# 04_Mechanical.net
KiCad netlist of a schematic drawn in Altium Designer
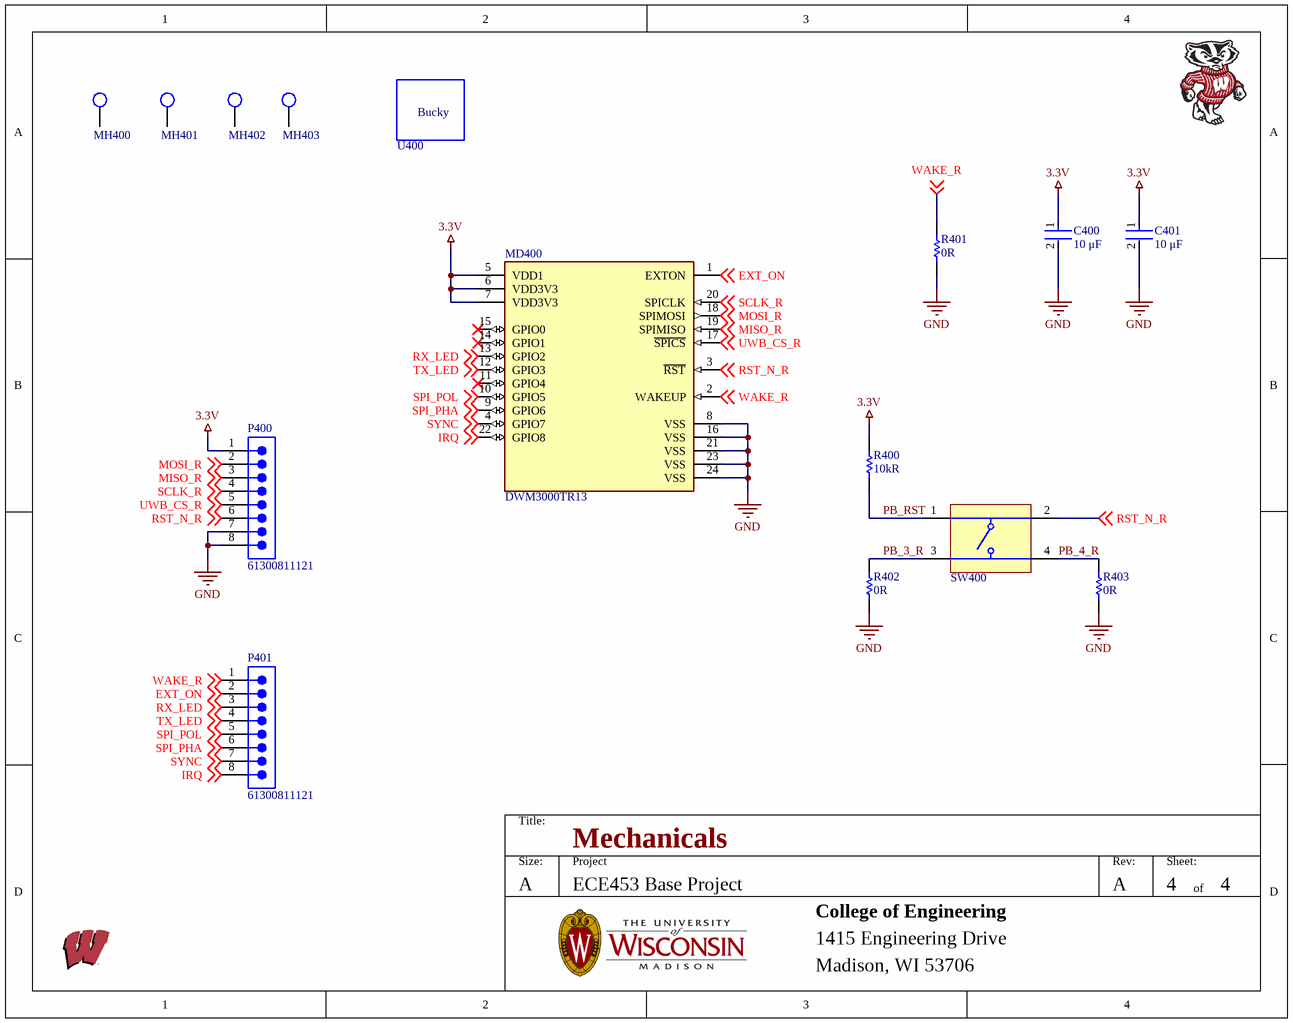
[diagram p0: 04_Mechanical.SchDoc]

(export (version "E")
  (design (tool "Eeschema 10.0.6"))
  (components
    (comp (ref "C400")
      (value "10 μF")
      (footprint "FP-C0805C-DG-MFG")
      (description "SMD Comm X5R, Ceramic, 10 uF, 10%, 10 V, X5R, SMD, MLCC, Temperature Stable, Class II, 0805")
      (fields (field (name "TOLERANCE") "10%"))
      (libsource (lib "Altium Content Vault") (part "11868f565c42a9108669ba33697ecf6"))
    )
    (comp (ref "C401")
      (value "10 μF")
      (footprint "FP-C0805C-DG-MFG")
      (description "SMD Comm X5R, Ceramic, 10 uF, 10%, 10 V, X5R, SMD, MLCC, Temperature Stable, Class II, 0805")
      (fields (field (name "TOLERANCE") "10%"))
      (libsource (lib "Altium Content Vault") (part "11868f565c42a9108669ba33697ecf6"))
    )
    (comp (ref "MD400")
      (value "DWM3000TR13")
      (footprint "FP-DWM3000TR13-MFG")
      (description "DWM3000 module Freq: 7.9872 GHz 6.8Mbps SPI 2.5-3.6V 8 GPIO's")
      (libsource (lib "Altium Content Vault") (part "094cfe914922597e69cd10df7811a9c"))
    )
    (comp (ref "MH400")
      (value "MHOLE_2_55MM")
      (footprint "MHOLE_2_55MM")
      (description "Mounting Holde")
      (fields (field (name "MANUFACTURER PART NUMBER") "UW MTHOLE"))
      (libsource (lib "ECE453_S24") (part "MHOLE_2_55MM"))
    )
    (comp (ref "MH401")
      (value "MHOLE_2_55MM")
      (footprint "MHOLE_2_55MM")
      (description "Mounting Holde")
      (fields (field (name "MANUFACTURER PART NUMBER") "UW MTHOLE"))
      (libsource (lib "ECE453_S24") (part "MHOLE_2_55MM"))
    )
    (comp (ref "MH402")
      (value "MHOLE_2_55MM")
      (footprint "MHOLE_2_55MM")
      (description "Mounting Holde")
      (fields (field (name "MANUFACTURER PART NUMBER") "UW MTHOLE"))
      (libsource (lib "ECE453_S24") (part "MHOLE_2_55MM"))
    )
    (comp (ref "MH403")
      (value "MHOLE_2_55MM")
      (footprint "MHOLE_2_55MM")
      (description "Mounting Holde")
      (fields (field (name "MANUFACTURER PART NUMBER") "UW MTHOLE"))
      (libsource (lib "ECE453_S24") (part "MHOLE_2_55MM"))
    )
    (comp (ref "P400")
      (value "61300811121")
      (footprint "61300811121")
      (fields (field (name "MANUFACTURER") "Wurth Electronics"))
      (libsource (lib "Altium Content Vault") (part "Header_Male_1R_08P"))
    )
    (comp (ref "P401")
      (value "61300811121")
      (footprint "61300811121")
      (fields (field (name "MANUFACTURER") "Wurth Electronics"))
      (libsource (lib "Altium Content Vault") (part "Header_Male_1R_08P"))
    )
    (comp (ref "R400")
      (value "10kR")
      (footprint "RESC2013X70X40ML20T20")
      (fields (field (name "MANUFACTURER") "Panasonic") (field (name "PART NUMBER") "ERJ-6ENF1002V"))
      (libsource (lib "Altium Content Vault") (part "RES"))
    )
    (comp (ref "R401")
      (value "0R")
      (footprint "RESC2013X70X40NL20T20")
      (description "Chip Resistor, 0 Ohm, +/- 1%, 0.125 W, -55 to 155 degC, 0805 (2012 Metric), RoHS, Tape and Reel")
      (fields (field (name "PARTNUMBER") "ERJ-6GEY0R00V") (field (name "TOLERANCE") "5%"))
      (libsource (lib "Altium Content Vault") (part "RES-2"))
    )
    (comp (ref "R402")
      (value "0R")
      (footprint "RESC2013X70X40NL20T20")
      (description "Chip Resistor, 0 Ohm, +/- 1%, 0.125 W, -55 to 155 degC, 0805 (2012 Metric), RoHS, Tape and Reel")
      (fields (field (name "PARTNUMBER") "ERJ-6GEY0R00V") (field (name "TOLERANCE") "5%"))
      (libsource (lib "Altium Content Vault") (part "RES-2"))
    )
    (comp (ref "R403")
      (value "0R")
      (footprint "RESC2013X70X40NL20T20")
      (description "Chip Resistor, 0 Ohm, +/- 1%, 0.125 W, -55 to 155 degC, 0805 (2012 Metric), RoHS, Tape and Reel")
      (fields (field (name "PARTNUMBER") "ERJ-6GEY0R00V") (field (name "TOLERANCE") "5%"))
      (libsource (lib "Altium Content Vault") (part "RES-2"))
    )
    (comp (ref "SW400")
      (value "~")
      (footprint "TECO-FSM4JSMA_V")
      (description "Swicth, SPST, 24 V, -35 to 85 degC, 4-Pin SMD, RoHS, Tape and Reel")
      (fields (field (name "MANUFACTURER") "TE Connectivity"))
      (libsource (lib "Altium Content Vault") (part "SW-SPST-4_A"))
    )
    (comp (ref "U400")
      (value "Bucky")
      (footprint "WalkingBucky")
      (description "Bucky Badger Image")
      (fields (field (name "MANUFACTURER PART NUMBER") "UW Bucky"))
      (libsource (lib "ECE453") (part "Bucky"))
    )
  )
  (nets
    (net (code "1") (name "/PB_3_R") (class "Default")
      (node (ref "R402") (pin "2") (pinfunction "2_2") (pintype "passive"))
      (node (ref "SW400") (pin "3") (pinfunction "3_3") (pintype "passive"))
    )
    (net (code "2") (name "/PB_4_R") (class "Default")
      (node (ref "R403") (pin "2") (pinfunction "2_2") (pintype "passive"))
      (node (ref "SW400") (pin "4") (pinfunction "4_4") (pintype "passive"))
    )
    (net (code "3") (name "/PB_RST") (class "Default")
      (node (ref "R400") (pin "1") (pinfunction "1_1") (pintype "passive"))
      (node (ref "SW400") (pin "1") (pinfunction "1_1") (pintype "passive"))
    )
    (net (code "4") (name "3.3V") (class "Default")
      (node (ref "C400") (pin "1") (pinfunction "1_1") (pintype "passive"))
      (node (ref "C401") (pin "1") (pinfunction "1_1") (pintype "passive"))
      (node (ref "MD400") (pin "5") (pinfunction "VDD1_5") (pintype "power_in"))
      (node (ref "MD400") (pin "6") (pinfunction "VDD3V3_6") (pintype "power_in"))
      (node (ref "MD400") (pin "7") (pinfunction "VDD3V3_7") (pintype "power_in"))
      (node (ref "P400") (pin "1") (pinfunction "1_1") (pintype "passive"))
      (node (ref "R400") (pin "2") (pinfunction "2_2") (pintype "passive"))
    )
    (net (code "5") (name "EXT_ON") (class "Default")
      (node (ref "MD400") (pin "1") (pinfunction "EXTON_1") (pintype "passive"))
      (node (ref "P401") (pin "2") (pinfunction "2_2") (pintype "passive"))
    )
    (net (code "6") (name "GND") (class "Default")
      (node (ref "C400") (pin "2") (pinfunction "2_2") (pintype "passive"))
      (node (ref "C401") (pin "2") (pinfunction "2_2") (pintype "passive"))
      (node (ref "MD400") (pin "16") (pinfunction "VSS_16") (pintype "power_in"))
      (node (ref "MD400") (pin "21") (pinfunction "VSS_21") (pintype "power_in"))
      (node (ref "MD400") (pin "23") (pinfunction "VSS_23") (pintype "power_in"))
      (node (ref "MD400") (pin "24") (pinfunction "VSS_24") (pintype "power_in"))
      (node (ref "MD400") (pin "8") (pinfunction "VSS_8") (pintype "power_in"))
      (node (ref "P400") (pin "7") (pinfunction "7_7") (pintype "passive"))
      (node (ref "P400") (pin "8") (pinfunction "8_8") (pintype "passive"))
      (node (ref "R401") (pin "2") (pinfunction "2_2") (pintype "passive"))
      (node (ref "R402") (pin "1") (pinfunction "1_1") (pintype "passive"))
      (node (ref "R403") (pin "1") (pinfunction "1_1") (pintype "passive"))
    )
    (net (code "7") (name "IRQ") (class "Default")
      (node (ref "MD400") (pin "22") (pinfunction "GPIO8_22") (pintype "bidirectional"))
      (node (ref "P401") (pin "8") (pinfunction "8_8") (pintype "passive"))
    )
    (net (code "8") (name "MISO_R") (class "Default")
      (node (ref "MD400") (pin "19") (pinfunction "SPIMISO_19") (pintype "input"))
      (node (ref "P400") (pin "3") (pinfunction "3_3") (pintype "passive"))
    )
    (net (code "9") (name "MOSI_R") (class "Default")
      (node (ref "MD400") (pin "18") (pinfunction "SPIMOSI_18") (pintype "output"))
      (node (ref "P400") (pin "2") (pinfunction "2_2") (pintype "passive"))
    )
    (net (code "10") (name "RST_N_R") (class "Default")
      (node (ref "MD400") (pin "3") (pinfunction "~{RST}_3") (pintype "input"))
      (node (ref "P400") (pin "6") (pinfunction "6_6") (pintype "passive"))
      (node (ref "SW400") (pin "2") (pinfunction "2_2") (pintype "passive"))
    )
    (net (code "11") (name "RX_LED") (class "Default")
      (node (ref "MD400") (pin "13") (pinfunction "GPIO2_13") (pintype "bidirectional"))
      (node (ref "P401") (pin "3") (pinfunction "3_3") (pintype "passive"))
    )
    (net (code "12") (name "SCLK_R") (class "Default")
      (node (ref "MD400") (pin "20") (pinfunction "SPICLK_20") (pintype "input"))
      (node (ref "P400") (pin "4") (pinfunction "4_4") (pintype "passive"))
    )
    (net (code "13") (name "SPI_PHA") (class "Default")
      (node (ref "MD400") (pin "9") (pinfunction "GPIO6_9") (pintype "bidirectional"))
      (node (ref "P401") (pin "6") (pinfunction "6_6") (pintype "passive"))
    )
    (net (code "14") (name "SPI_POL") (class "Default")
      (node (ref "MD400") (pin "10") (pinfunction "GPIO5_10") (pintype "bidirectional"))
      (node (ref "P401") (pin "5") (pinfunction "5_5") (pintype "passive"))
    )
    (net (code "15") (name "SYNC") (class "Default")
      (node (ref "MD400") (pin "4") (pinfunction "GPIO7_4") (pintype "bidirectional"))
      (node (ref "P401") (pin "7") (pinfunction "7_7") (pintype "passive"))
    )
    (net (code "16") (name "TX_LED") (class "Default")
      (node (ref "MD400") (pin "12") (pinfunction "GPIO3_12") (pintype "bidirectional"))
      (node (ref "P401") (pin "4") (pinfunction "4_4") (pintype "passive"))
    )
    (net (code "17") (name "UWB_CS_R") (class "Default")
      (node (ref "MD400") (pin "17") (pinfunction "~{SPICS}_17") (pintype "input"))
      (node (ref "P400") (pin "5") (pinfunction "5_5") (pintype "passive"))
    )
    (net (code "18") (name "WAKE_R") (class "Default")
      (node (ref "MD400") (pin "2") (pinfunction "WAKEUP_2") (pintype "input"))
      (node (ref "P401") (pin "1") (pinfunction "1_1") (pintype "passive"))
      (node (ref "R401") (pin "1") (pinfunction "1_1") (pintype "passive"))
    )
    (net (code "19") (name "unconnected-(MD400-GPIO0-Pad15)") (class "Default")
      (node (ref "MD400") (pin "15") (pinfunction "GPIO0_15") (pintype "bidirectional+no_connect"))
    )
    (net (code "20") (name "unconnected-(MD400-GPIO1-Pad14)") (class "Default")
      (node (ref "MD400") (pin "14") (pinfunction "GPIO1_14") (pintype "bidirectional+no_connect"))
    )
    (net (code "21") (name "unconnected-(MD400-GPIO4-Pad11)") (class "Default")
      (node (ref "MD400") (pin "11") (pinfunction "GPIO4_11") (pintype "bidirectional+no_connect"))
    )
    (net (code "22") (name "unconnected-(MH400-Pad1)") (class "Default")
      (node (ref "MH400") (pin "1") (pintype "passive"))
    )
    (net (code "23") (name "unconnected-(MH401-Pad1)") (class "Default")
      (node (ref "MH401") (pin "1") (pintype "passive"))
    )
    (net (code "24") (name "unconnected-(MH402-Pad1)") (class "Default")
      (node (ref "MH402") (pin "1") (pintype "passive"))
    )
    (net (code "25") (name "unconnected-(MH403-Pad1)") (class "Default")
      (node (ref "MH403") (pin "1") (pintype "passive"))
    )
  )
)
